# 1uprava3.net
KiCad netlist of a schematic drawn in EAGLE
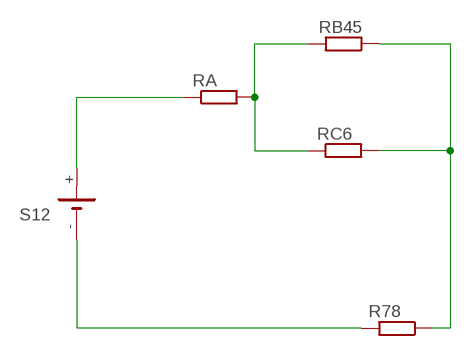
[diagram p0: schematic, sheet 1]

(export (version "E")
  (design (tool "Eeschema 10.0.6"))
  (components
    (comp (ref "R78")
      (value "355R")
      (footprint "eagle-import:0204_7")
      (libsource (lib "eagle-import") (part "R-EU_0204/7"))
    )
    (comp (ref "RA")
      (value "680R")
      (footprint "eagle-import:0204_7")
      (libsource (lib "eagle-import") (part "R-EU_0204/7"))
    )
    (comp (ref "RB45")
      (value "260R")
      (footprint "eagle-import:0204_7")
      (libsource (lib "eagle-import") (part "R-EU_0204/7"))
    )
    (comp (ref "RC6")
      (value "600R")
      (footprint "eagle-import:0204_7")
      (libsource (lib "eagle-import") (part "R-EU_0204/7"))
    )
    (comp (ref "S12")
      (value "135V")
      (footprint "eagle-import:CH291-1220LF")
      (libsource (lib "eagle-import") (part "CH291-1220LF"))
    )
  )
  (nets
    (net (code "1") (name "Net-(R78-Pad1)") (class "Default")
      (node (ref "R78") (pin "1") (pinfunction "1_1") (pintype "passive"))
      (node (ref "RB45") (pin "1") (pinfunction "1_1") (pintype "passive"))
      (node (ref "RC6") (pin "2") (pinfunction "2_2") (pintype "passive"))
    )
    (net (code "2") (name "Net-(R78-Pad2)") (class "Default")
      (node (ref "R78") (pin "2") (pinfunction "2_2") (pintype "passive"))
      (node (ref "S12") (pin "-") (pinfunction "-_-") (pintype "passive"))
    )
    (net (code "3") (name "Net-(RA-Pad1)") (class "Default")
      (node (ref "RA") (pin "1") (pinfunction "1_1") (pintype "passive"))
      (node (ref "S12") (pin "+") (pinfunction "+_+") (pintype "passive"))
    )
    (net (code "4") (name "Net-(RA-Pad2)") (class "Default")
      (node (ref "RA") (pin "2") (pinfunction "2_2") (pintype "passive"))
      (node (ref "RB45") (pin "2") (pinfunction "2_2") (pintype "passive"))
      (node (ref "RC6") (pin "1") (pinfunction "1_1") (pintype "passive"))
    )
  )
)
